# 3_2.net
KiCad netlist of a schematic drawn in Altium Designer
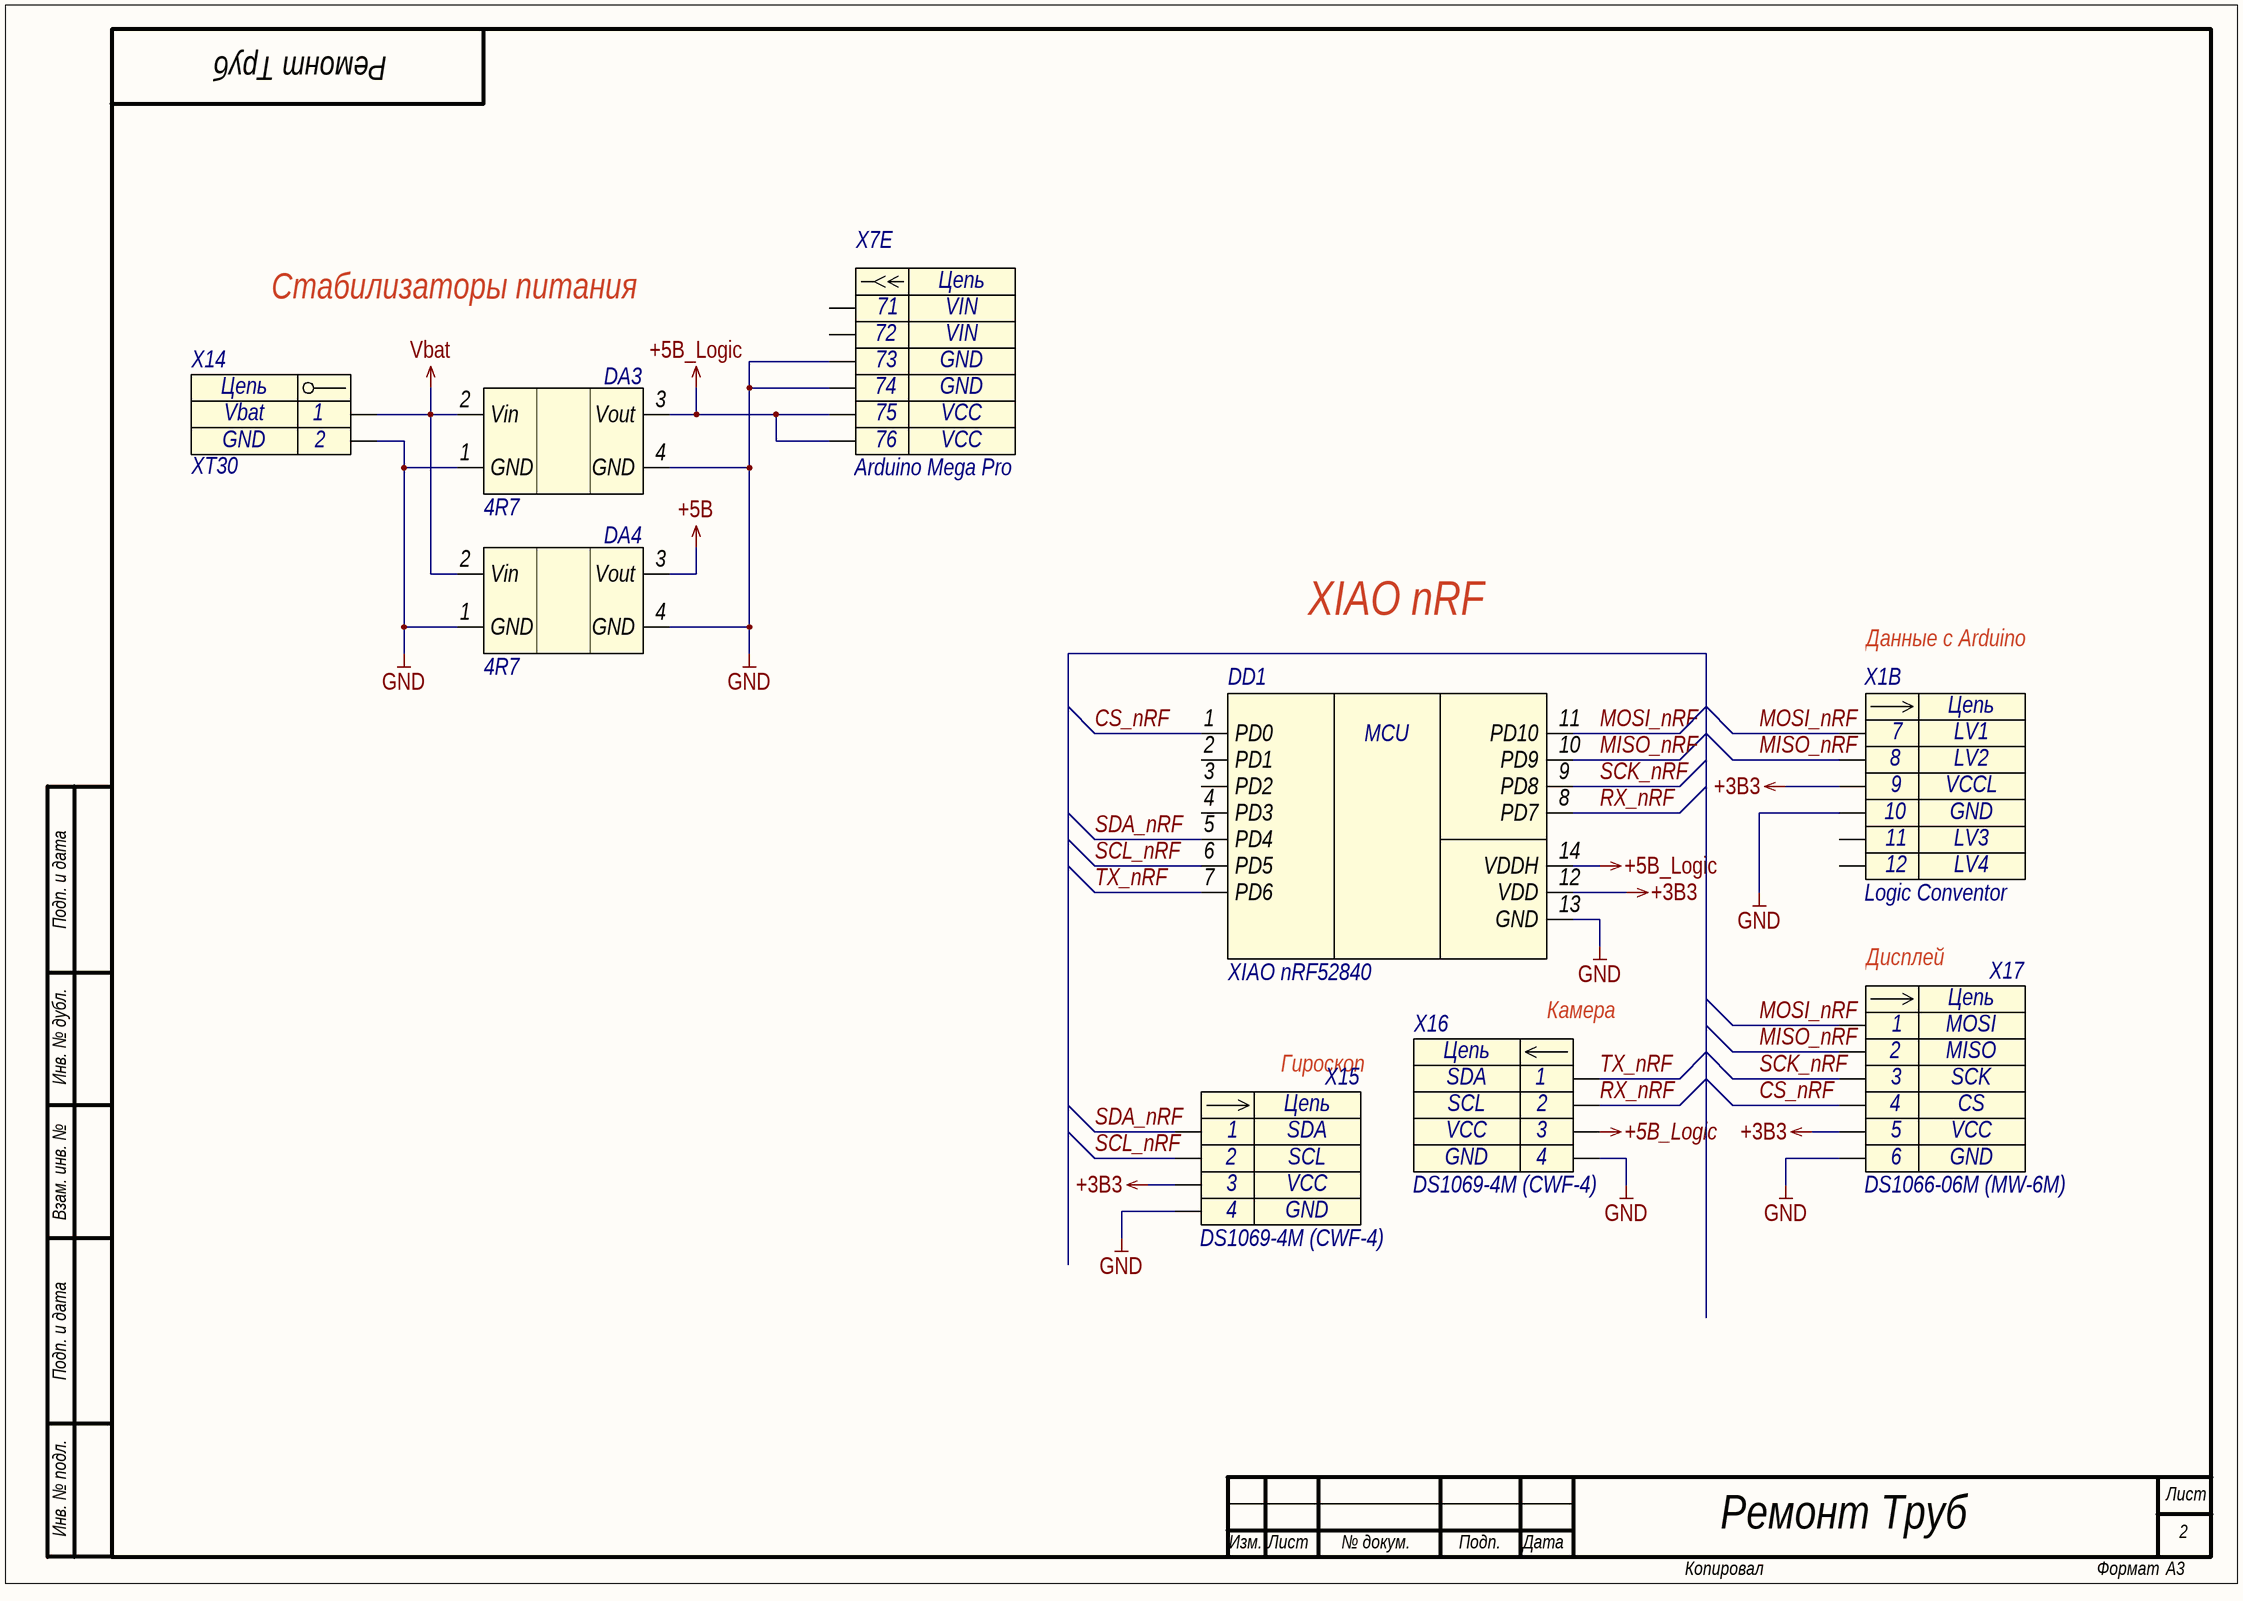
[diagram p0: Э3_2.SchDoc]

(export (version "E")
  (design (tool "Eeschema 10.0.6"))
  (components
    (comp (ref "DA3")
      (value "4R7")
      (footprint "mini360")
      (description "Линейный стабилизатор напряжения 14.4В -> 5В")
      (fields (field (name "MANUFACTURER") "China") (field (name "NAME") "4R7"))
      (libsource (lib "ics") (part "4R7"))
    )
    (comp (ref "DA4")
      (value "4R7")
      (footprint "mini360")
      (description "Линейный стабилизатор напряжения 14.4В -> 5В")
      (fields (field (name "MANUFACTURER") "China") (field (name "NAME") "4R7"))
      (libsource (lib "ics") (part "4R7"))
    )
    (comp (ref "DD1")
      (value "XIAO nRF52840")
      (footprint "Seeed Studio XIAO nRF52840")
      (description "Микроконтроллер nRF52840")
      (libsource (lib "MCU") (part "XIAO nRF52840"))
    )
    (comp (ref "X1")
      (value "Logic Conventor")
      (footprint "LOGIC CONVENTOR")
      (description "Преобразователь уровней")
      (fields (field (name "NAME") "Logic Conventor"))
      (libsource (lib "headers") (part "Logic Conventor"))
    )
    (comp (ref "X7")
      (value "Arduino Mega Pro")
      (footprint "Arduino Mega Pro Mini")
      (description "Arduino Mega Pro Mini")
      (fields (field (name "NAME") "Arduino Mega Pro"))
      (libsource (lib "headers") (part "Arduino Mega Pro Mini"))
    )
    (comp (ref "X14")
      (value "XT30")
      (footprint "XT30 - duplicate")
      (fields (field (name "NAME") "XT30"))
      (libsource (lib "headers") (part "XT30"))
    )
    (comp (ref "X15")
      (value "DS1069-4M (CWF-4)")
      (footprint "CWF-4")
      (description "Разъем - 4 конт. прямая вилка на плату")
      (fields (field (name "NAME") "DS1069-4M (CWF-4)"))
      (libsource (lib "") (part "CWF-4_1"))
    )
    (comp (ref "X16")
      (value "DS1069-4M (CWF-4)")
      (footprint "CWF-4")
      (description "Разъем - 4 конт. прямая вилка на плату")
      (fields (field (name "NAME") "DS1069-4M (CWF-4)"))
      (libsource (lib "headers") (part "CWF-4"))
    )
    (comp (ref "X17")
      (value "DS1066-06M (MW-6M)")
      (footprint "MW-6M")
      (description "Разъем - 6 конт. прямая вилка на плату")
      (fields (field (name "NAME") "DS1066-06M (MW-6M)"))
      (libsource (lib "headers") (part "MW-6M"))
    )
  )
  (nets
    (net (code "1") (name "+3B3") (class "Default")
      (node (ref "DD1") (pin "12") (pinfunction "VDD_12") (pintype "passive"))
      (node (ref "X1") (pin "9") (pinfunction "9_9") (pintype "passive"))
      (node (ref "X15") (pin "3") (pinfunction "3_3") (pintype "passive"))
      (node (ref "X17") (pin "5") (pinfunction "5_5") (pintype "passive"))
    )
    (net (code "2") (name "+5B") (class "Default")
      (node (ref "DA4") (pin "3") (pinfunction "Vout_3") (pintype "passive"))
    )
    (net (code "3") (name "+5B_Logic") (class "Default")
      (node (ref "DA3") (pin "3") (pinfunction "Vout_3") (pintype "passive"))
      (node (ref "DD1") (pin "14") (pinfunction "VDDH_14") (pintype "passive"))
      (node (ref "X16") (pin "3") (pinfunction "3_3") (pintype "passive"))
      (node (ref "X7") (pin "75") (pinfunction "75_75") (pintype "passive"))
      (node (ref "X7") (pin "76") (pinfunction "76_76") (pintype "passive"))
    )
    (net (code "4") (name "/CS_nRF") (class "Default")
      (node (ref "DD1") (pin "1") (pinfunction "PD0_1") (pintype "passive"))
      (node (ref "X17") (pin "4") (pinfunction "4_4") (pintype "passive"))
    )
    (net (code "5") (name "/MISO_nRF") (class "Default")
      (node (ref "DD1") (pin "10") (pinfunction "PD9_10") (pintype "passive"))
      (node (ref "X1") (pin "8") (pinfunction "8_8") (pintype "passive"))
      (node (ref "X17") (pin "2") (pinfunction "2_2") (pintype "passive"))
    )
    (net (code "6") (name "/MOSI_nRF") (class "Default")
      (node (ref "DD1") (pin "11") (pinfunction "PD10_11") (pintype "passive"))
      (node (ref "X1") (pin "7") (pinfunction "7_7") (pintype "passive"))
      (node (ref "X17") (pin "1") (pinfunction "1_1") (pintype "passive"))
    )
    (net (code "7") (name "/RX_nRF") (class "Default")
      (node (ref "DD1") (pin "8") (pinfunction "PD7_8") (pintype "passive"))
      (node (ref "X16") (pin "2") (pinfunction "2_2") (pintype "passive"))
    )
    (net (code "8") (name "/SCK_nRF") (class "Default")
      (node (ref "DD1") (pin "9") (pinfunction "PD8_9") (pintype "passive"))
      (node (ref "X17") (pin "3") (pinfunction "3_3") (pintype "passive"))
    )
    (net (code "9") (name "/SCL_nRF") (class "Default")
      (node (ref "DD1") (pin "6") (pinfunction "PD5_6") (pintype "passive"))
      (node (ref "X15") (pin "2") (pinfunction "2_2") (pintype "passive"))
    )
    (net (code "10") (name "/SDA_nRF") (class "Default")
      (node (ref "DD1") (pin "5") (pinfunction "PD4_5") (pintype "passive"))
      (node (ref "X15") (pin "1") (pinfunction "1_1") (pintype "passive"))
    )
    (net (code "11") (name "/TX_nRF") (class "Default")
      (node (ref "DD1") (pin "7") (pinfunction "PD6_7") (pintype "passive"))
      (node (ref "X16") (pin "1") (pinfunction "1_1") (pintype "passive"))
    )
    (net (code "12") (name "GND") (class "Default")
      (node (ref "DA3") (pin "1") (pinfunction "GND_1") (pintype "passive"))
      (node (ref "DA3") (pin "4") (pinfunction "GND_4") (pintype "passive"))
      (node (ref "DA4") (pin "1") (pinfunction "GND_1") (pintype "passive"))
      (node (ref "DA4") (pin "4") (pinfunction "GND_4") (pintype "passive"))
      (node (ref "DD1") (pin "13") (pinfunction "GND_13") (pintype "passive"))
      (node (ref "X1") (pin "10") (pinfunction "10_10") (pintype "passive"))
      (node (ref "X14") (pin "2") (pinfunction "2_2") (pintype "passive"))
      (node (ref "X15") (pin "4") (pinfunction "4_4") (pintype "passive"))
      (node (ref "X16") (pin "4") (pinfunction "4_4") (pintype "passive"))
      (node (ref "X17") (pin "6") (pinfunction "6_6") (pintype "passive"))
      (node (ref "X7") (pin "73") (pinfunction "73_73") (pintype "passive"))
      (node (ref "X7") (pin "74") (pinfunction "74_74") (pintype "passive"))
    )
    (net (code "13") (name "Vbat") (class "Default")
      (node (ref "DA3") (pin "2") (pinfunction "Vin_2") (pintype "passive"))
      (node (ref "DA4") (pin "2") (pinfunction "Vin_2") (pintype "passive"))
      (node (ref "X14") (pin "1") (pinfunction "1_1") (pintype "passive"))
    )
    (net (code "14") (name "unconnected-(DD1-PD1-Pad2)") (class "Default")
      (node (ref "DD1") (pin "2") (pinfunction "PD1_2") (pintype "passive"))
    )
    (net (code "15") (name "unconnected-(DD1-PD2-Pad3)") (class "Default")
      (node (ref "DD1") (pin "3") (pinfunction "PD2_3") (pintype "passive"))
    )
    (net (code "16") (name "unconnected-(DD1-PD3-Pad4)") (class "Default")
      (node (ref "DD1") (pin "4") (pinfunction "PD3_4") (pintype "passive"))
    )
    (net (code "17") (name "unconnected-(X1-Pad11)") (class "Default")
      (node (ref "X1") (pin "11") (pinfunction "11_11") (pintype "passive"))
    )
    (net (code "18") (name "unconnected-(X1-Pad12)") (class "Default")
      (node (ref "X1") (pin "12") (pinfunction "12_12") (pintype "passive"))
    )
    (net (code "19") (name "unconnected-(X7-Pad71)") (class "Default")
      (node (ref "X7") (pin "71") (pinfunction "71_71") (pintype "passive"))
    )
    (net (code "20") (name "unconnected-(X7-Pad72)") (class "Default")
      (node (ref "X7") (pin "72") (pinfunction "72_72") (pintype "passive"))
    )
  )
)
